# WearableMetronome.net
KiCad netlist of a schematic drawn in EAGLE
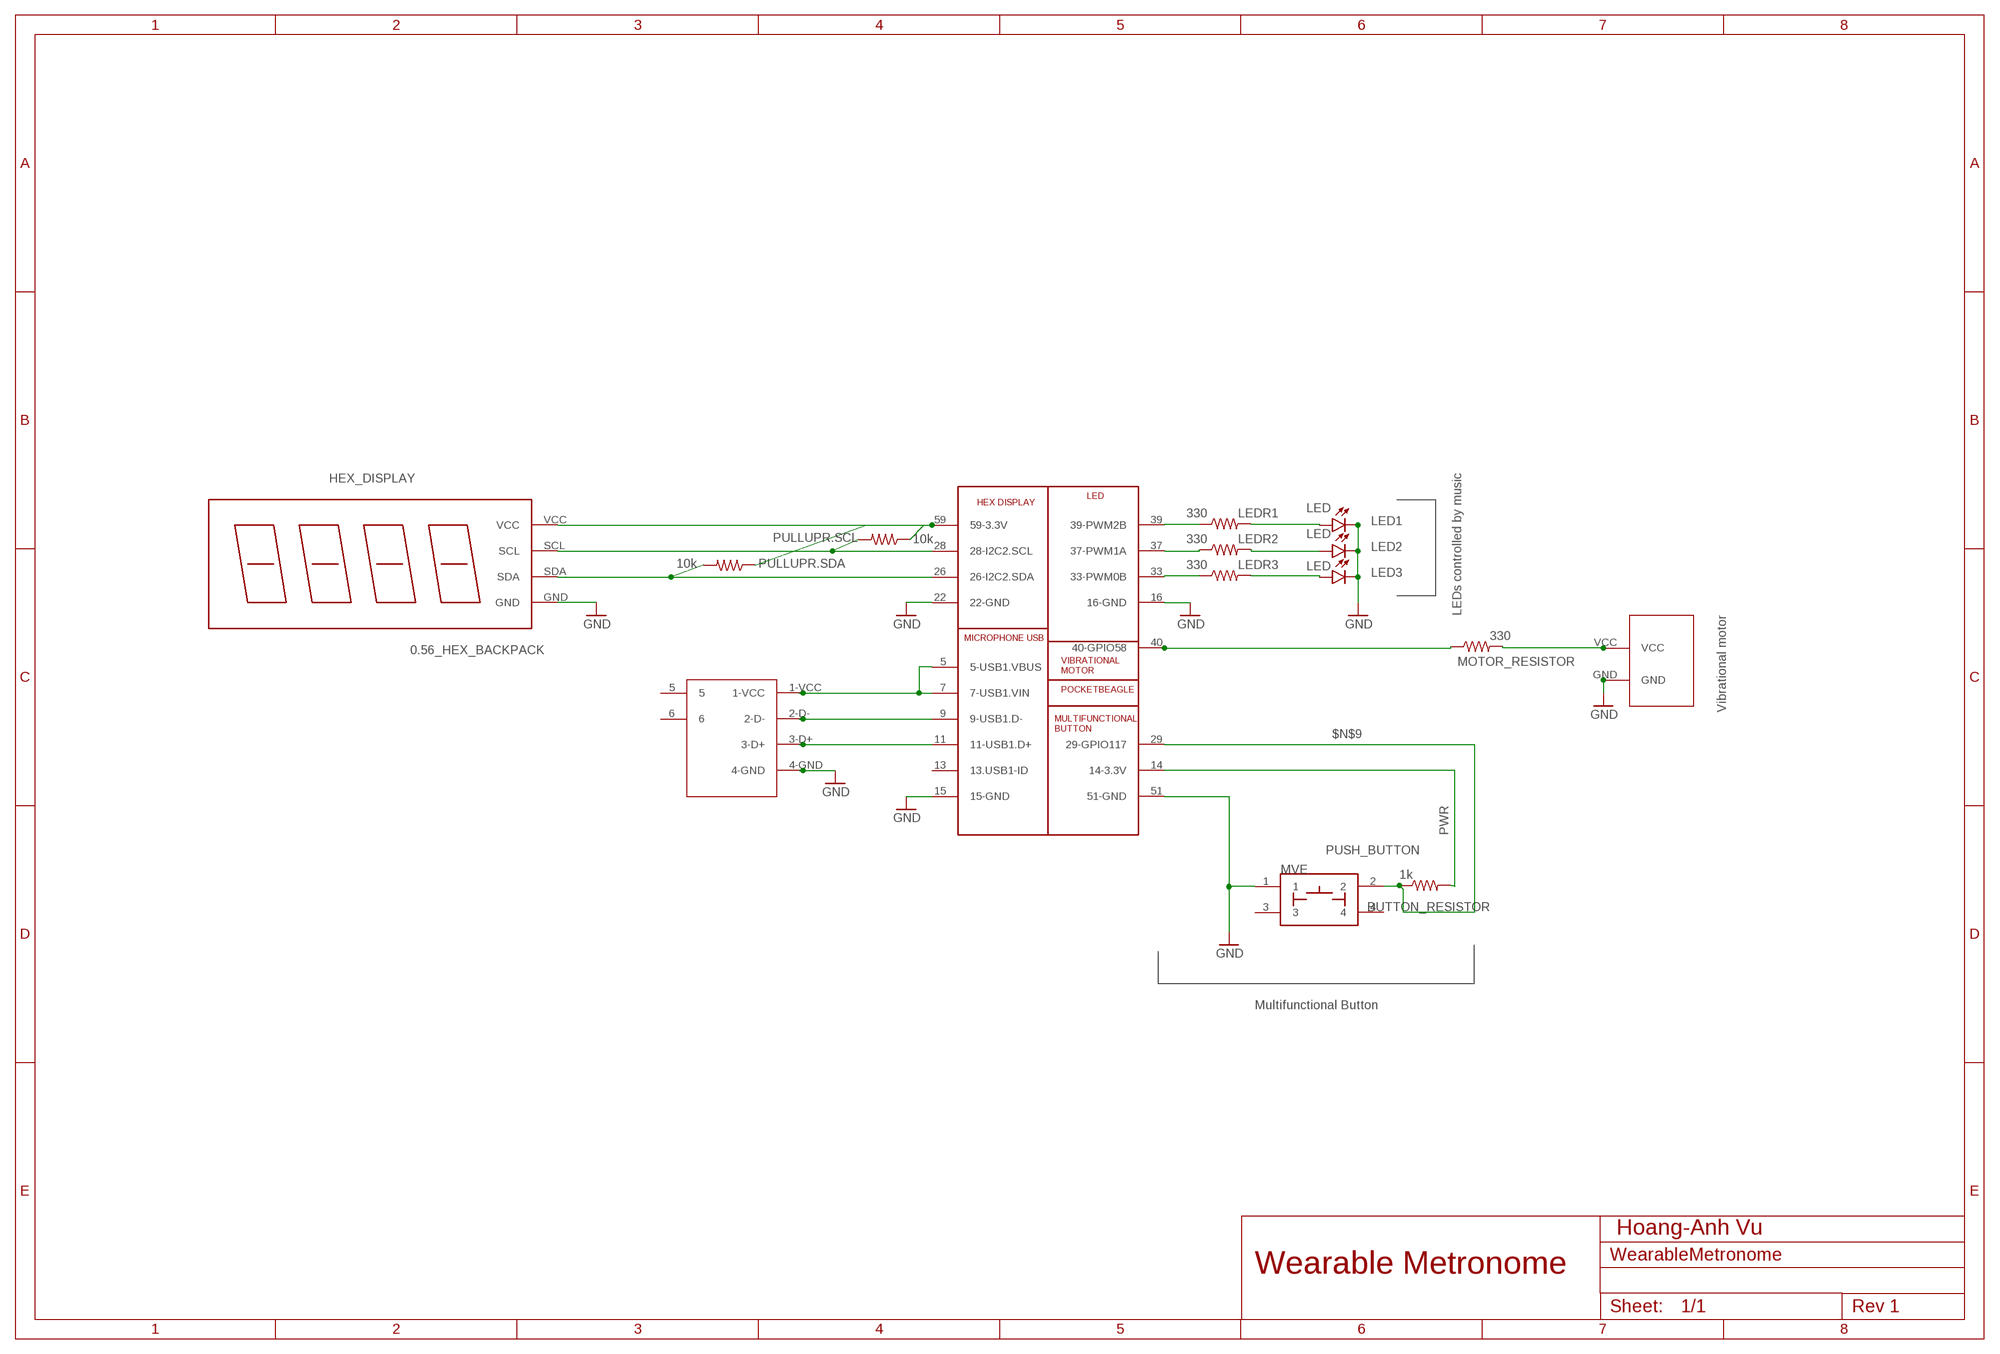
[diagram p0: schematic, sheet 1]

(export (version "E")
  (design (tool "Eeschema 10.0.6"))
  (components
    (comp (ref "BUTTON_RESISTOR")
      (value "1k")
      (footprint "eagle-import:R0603")
      (libsource (lib "eagle-import") (part "R_R0603"))
    )
    (comp (ref "HEX_DISPLAY")
      (value "0.56_HEX_BACKPACK")
      (footprint "eagle-import:0.56_HEX_BACKPACK")
      (libsource (lib "eagle-import") (part "0.56_HEX_BACKPACK"))
    )
    (comp (ref "LED1")
      (value "LED")
      (footprint "eagle-import:EIA-STD")
      (libsource (lib "eagle-import") (part "LED"))
    )
    (comp (ref "LED2")
      (value "LED")
      (footprint "eagle-import:EIA-STD")
      (libsource (lib "eagle-import") (part "LED"))
    )
    (comp (ref "LED3")
      (value "LED")
      (footprint "eagle-import:EIA-STD")
      (libsource (lib "eagle-import") (part "LED"))
    )
    (comp (ref "LEDR1")
      (value "330")
      (footprint "eagle-import:R0603")
      (libsource (lib "eagle-import") (part "R_R0603"))
    )
    (comp (ref "LEDR2")
      (value "330")
      (footprint "eagle-import:R0603")
      (libsource (lib "eagle-import") (part "R_R0603"))
    )
    (comp (ref "LEDR3")
      (value "330")
      (footprint "eagle-import:R0603")
      (libsource (lib "eagle-import") (part "R_R0603"))
    )
    (comp (ref "MOTOR_RESISTOR")
      (value "330")
      (footprint "eagle-import:R0603")
      (libsource (lib "eagle-import") (part "R_R0603"))
    )
    (comp (ref "MVE")
      (value "PUSH_BUTTON")
      (footprint "eagle-import:BUTTON_12.5MM")
      (libsource (lib "eagle-import") (part "PUSH_BUTTON"))
    )
    (comp (ref "PULLUPR.SCL")
      (value "10k")
      (footprint "eagle-import:R0603")
      (libsource (lib "eagle-import") (part "R_R0603"))
    )
    (comp (ref "PULLUPR.SDA")
      (value "10k")
      (footprint "eagle-import:R0603")
      (libsource (lib "eagle-import") (part "R_R0603"))
    )
    (comp (ref "U$1")
      (value "USBAFEMALE")
      (footprint "eagle-import:USBAFEMALE")
      (libsource (lib "eagle-import") (part "USBAFEMALE"))
    )
    (comp (ref "U$2")
      (value "VIBRATIONALMOTOR")
      (footprint "eagle-import:VIBRATIONALMOTOR")
      (libsource (lib "eagle-import") (part "VIBRATIONALMOTOR"))
    )
    (comp (ref "U$3")
      (value "POCKETBEAGLE_HOANG")
      (footprint "eagle-import:POCKETBEAGLE_HOANG")
      (libsource (lib "eagle-import") (part "POCKETBEAGLE_HOANG"))
    )
  )
  (nets
    (net (code "1") (name "/$N$9") (class "Default")
      (node (ref "BUTTON_RESISTOR") (pin "1") (pinfunction "1_1") (pintype "passive"))
      (node (ref "MVE") (pin "2") (pinfunction "2_2") (pintype "bidirectional"))
      (node (ref "U$3") (pin "29") (pinfunction "29-GPIO117_29") (pintype "bidirectional"))
    )
    (net (code "2") (name "/PWR") (class "Default")
      (node (ref "BUTTON_RESISTOR") (pin "2") (pinfunction "2_2") (pintype "passive"))
      (node (ref "HEX_DISPLAY") (pin "VCC") (pinfunction "VCC_VCC") (pintype "power_in"))
      (node (ref "PULLUPR.SCL") (pin "1") (pinfunction "1_1") (pintype "passive"))
      (node (ref "PULLUPR.SDA") (pin "1") (pinfunction "1_1") (pintype "passive"))
      (node (ref "U$3") (pin "14") (pinfunction "14-3.3V_14") (pintype "power_in"))
      (node (ref "U$3") (pin "59") (pinfunction "59-3.3V_59") (pintype "power_in"))
    )
    (net (code "3") (name "GND") (class "Default")
      (node (ref "HEX_DISPLAY") (pin "GND") (pinfunction "GND_GND") (pintype "bidirectional"))
      (node (ref "LED1") (pin "P$2") (pinfunction "C_P$2") (pintype "passive"))
      (node (ref "LED2") (pin "P$2") (pinfunction "C_P$2") (pintype "passive"))
      (node (ref "LED3") (pin "P$2") (pinfunction "C_P$2") (pintype "passive"))
      (node (ref "MVE") (pin "1") (pinfunction "1_1") (pintype "bidirectional"))
      (node (ref "U$1") (pin "4-GND") (pinfunction "4-GND_4-GND") (pintype "bidirectional"))
      (node (ref "U$2") (pin "GND") (pinfunction "GND_GND") (pintype "bidirectional"))
      (node (ref "U$3") (pin "15") (pinfunction "15-GND_15") (pintype "power_in"))
      (node (ref "U$3") (pin "16") (pinfunction "16-GND_16") (pintype "power_in"))
      (node (ref "U$3") (pin "22") (pinfunction "22-GND_22") (pintype "power_in"))
      (node (ref "U$3") (pin "51") (pinfunction "51-GND_51") (pintype "power_in"))
    )
    (net (code "4") (name "Net-(LED1-A)") (class "Default")
      (node (ref "LED1") (pin "P$1") (pinfunction "A_P$1") (pintype "passive"))
      (node (ref "LEDR1") (pin "2") (pinfunction "2_2") (pintype "passive"))
    )
    (net (code "5") (name "Net-(LED2-A)") (class "Default")
      (node (ref "LED2") (pin "P$1") (pinfunction "A_P$1") (pintype "passive"))
      (node (ref "LEDR2") (pin "2") (pinfunction "2_2") (pintype "passive"))
    )
    (net (code "6") (name "Net-(LED3-A)") (class "Default")
      (node (ref "LED3") (pin "P$1") (pinfunction "A_P$1") (pintype "passive"))
      (node (ref "LEDR3") (pin "2") (pinfunction "2_2") (pintype "passive"))
    )
    (net (code "7") (name "Net-(MOTOR_RESISTOR-Pad2)") (class "Default")
      (node (ref "MOTOR_RESISTOR") (pin "2") (pinfunction "2_2") (pintype "passive"))
      (node (ref "U$2") (pin "VCC") (pinfunction "VCC_VCC") (pintype "bidirectional"))
    )
    (net (code "8") (name "Net-(U$3-5-USB1.VBUS)") (class "Default")
      (node (ref "U$1") (pin "1-VCC") (pinfunction "1-VCC_1-VCC") (pintype "bidirectional"))
      (node (ref "U$3") (pin "5") (pinfunction "5-USB1.VBUS_5") (pintype "bidirectional"))
      (node (ref "U$3") (pin "7") (pinfunction "7-USB1.VIN_7") (pintype "bidirectional"))
    )
    (net (code "9") (name "Net-(U$3-9-USB1.D-)") (class "Default")
      (node (ref "U$1") (pin "2-D-") (pinfunction "2-D-_2-D-") (pintype "bidirectional"))
      (node (ref "U$3") (pin "9") (pinfunction "9-USB1.D-_9") (pintype "bidirectional"))
    )
    (net (code "10") (name "Net-(U$3-11-USB1.D+)") (class "Default")
      (node (ref "U$1") (pin "3-D+") (pinfunction "3-D+_3-D+") (pintype "bidirectional"))
      (node (ref "U$3") (pin "11") (pinfunction "11-USB1.D+_11") (pintype "bidirectional"))
    )
    (net (code "11") (name "Net-(U$3-26-I2C2.SDA)") (class "Default")
      (node (ref "HEX_DISPLAY") (pin "SDA") (pinfunction "SDA_SDA") (pintype "bidirectional"))
      (node (ref "PULLUPR.SDA") (pin "2") (pinfunction "2_2") (pintype "passive"))
      (node (ref "U$3") (pin "26") (pinfunction "26-I2C2.SDA_26") (pintype "bidirectional"))
    )
    (net (code "12") (name "Net-(U$3-28-I2C2.SCL)") (class "Default")
      (node (ref "HEX_DISPLAY") (pin "SCL") (pinfunction "SCL_SCL") (pintype "bidirectional"))
      (node (ref "PULLUPR.SCL") (pin "2") (pinfunction "2_2") (pintype "passive"))
      (node (ref "U$3") (pin "28") (pinfunction "28-I2C2.SCL_28") (pintype "bidirectional"))
    )
    (net (code "13") (name "Net-(U$3-33-PWM0B)") (class "Default")
      (node (ref "LEDR3") (pin "1") (pinfunction "1_1") (pintype "passive"))
      (node (ref "U$3") (pin "33") (pinfunction "33-PWM0B_33") (pintype "bidirectional"))
    )
    (net (code "14") (name "Net-(U$3-37-PWM1A)") (class "Default")
      (node (ref "LEDR2") (pin "1") (pinfunction "1_1") (pintype "passive"))
      (node (ref "U$3") (pin "37") (pinfunction "37-PWM1A_37") (pintype "bidirectional"))
    )
    (net (code "15") (name "Net-(U$3-39-PWM2B)") (class "Default")
      (node (ref "LEDR1") (pin "1") (pinfunction "1_1") (pintype "passive"))
      (node (ref "U$3") (pin "39") (pinfunction "39-PWM2B_39") (pintype "bidirectional"))
    )
    (net (code "16") (name "Net-(U$3-40-GPIO58)") (class "Default")
      (node (ref "MOTOR_RESISTOR") (pin "1") (pinfunction "1_1") (pintype "passive"))
      (node (ref "U$3") (pin "40") (pinfunction "40-GPIO58_40") (pintype "bidirectional"))
    )
    (net (code "17") (name "unconnected-(MVE-Pad3)") (class "Default")
      (node (ref "MVE") (pin "3") (pinfunction "3_3") (pintype "bidirectional"))
    )
    (net (code "18") (name "unconnected-(MVE-Pad4)") (class "Default")
      (node (ref "MVE") (pin "4") (pinfunction "4_4") (pintype "bidirectional"))
    )
    (net (code "19") (name "unconnected-(U$1-Pad5)") (class "Default")
      (node (ref "U$1") (pin "5") (pinfunction "5_5") (pintype "bidirectional"))
    )
    (net (code "20") (name "unconnected-(U$1-Pad6)") (class "Default")
      (node (ref "U$1") (pin "6") (pinfunction "6_6") (pintype "bidirectional"))
    )
    (net (code "21") (name "unconnected-(U$3-13.USB1-ID-Pad13)") (class "Default")
      (node (ref "U$3") (pin "13") (pinfunction "13.USB1-ID_13") (pintype "bidirectional"))
    )
  )
)
